# PowerInjectorSchematic.net
KiCad netlist of a schematic drawn in Altium Designer
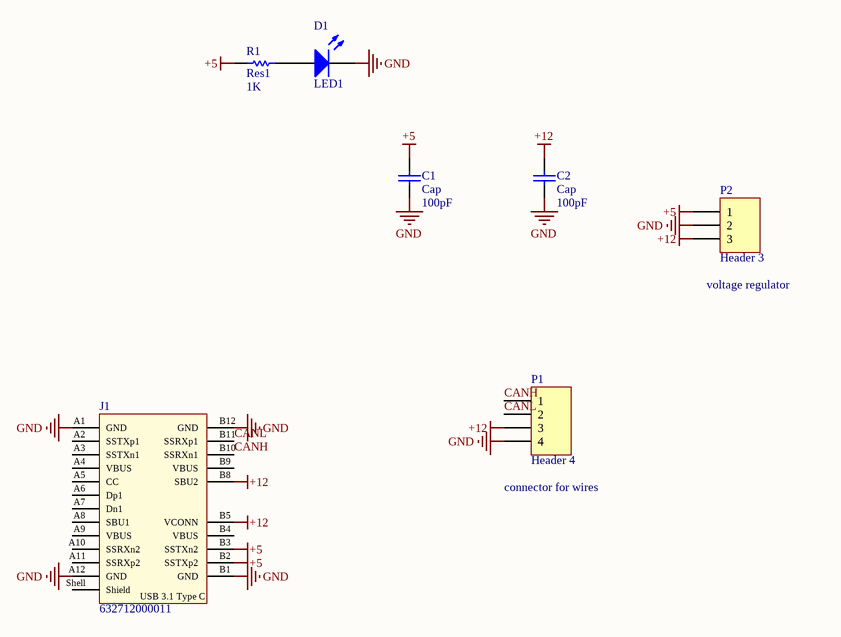
[diagram p0: PowerInjectorSchematic.SchDoc]

(export (version "E")
  (design (tool "Eeschema 10.0.6"))
  (components
    (comp (ref "C1")
      (value "Cap")
      (footprint "RAD-0.3")
      (description "Capacitor")
      (fields (field (name "ALTIUM_VALUE") "100pF") (field (name "PUBLISHER") "Altium Limited"))
      (libsource (lib "Miscellaneous Devices") (part "Cap"))
    )
    (comp (ref "C2")
      (value "Cap")
      (footprint "RAD-0.3")
      (description "Capacitor")
      (fields (field (name "ALTIUM_VALUE") "100pF") (field (name "PUBLISHER") "Altium Limited"))
      (libsource (lib "Miscellaneous Devices") (part "Cap"))
    )
    (comp (ref "D1")
      (value "LED1")
      (footprint "LED-1")
      (description "Typical RED GaAs LED")
      (fields (field (name "PUBLISHER") "Altium Limited"))
      (libsource (lib "Miscellaneous Devices") (part "LED1"))
    )
    (comp (ref "J1")
      (value "632712000011")
      (footprint "632712000011")
      (description "USB 3.1 Type C Plug Horizontal SMT WR-COM")
      (fields (field (name "PUBLISHER") "Wurth Elektronik"))
      (libsource (lib "ALTIUM-WR-COM-rev17a (1)") (part "632712000011"))
    )
    (comp (ref "P1")
      (value "Header 4")
      (footprint "HDR1X4")
      (description "Header, 4-Pin")
      (fields (field (name "PUBLISHER") "Altium Limited"))
      (libsource (lib "Miscellaneous Connectors") (part "Header 4"))
    )
    (comp (ref "P2")
      (value "Header 3")
      (footprint "HDR1X3")
      (description "Header, 3-Pin")
      (fields (field (name "PUBLISHER") "Altium Limited"))
      (libsource (lib "Miscellaneous Connectors") (part "Header 3"))
    )
    (comp (ref "R1")
      (value "Res1")
      (footprint "AXIAL-0.3")
      (description "Resistor")
      (fields (field (name "ALTIUM_VALUE") "1K") (field (name "PUBLISHER") "Altium Limited"))
      (libsource (lib "Miscellaneous Devices") (part "Res1"))
    )
  )
  (nets
    (net (code "1") (name "+5") (class "Default")
      (node (ref "C1") (pin "2") (pinfunction "2_2") (pintype "passive"))
      (node (ref "J1") (pin "B2") (pinfunction "SSTXp2_B2") (pintype "passive"))
      (node (ref "J1") (pin "B3") (pinfunction "SSTXn2_B3") (pintype "passive"))
      (node (ref "P2") (pin "1") (pinfunction "1_1") (pintype "passive"))
      (node (ref "R1") (pin "1") (pinfunction "1_1") (pintype "passive"))
    )
    (net (code "2") (name "+12") (class "Default")
      (node (ref "C2") (pin "2") (pinfunction "2_2") (pintype "passive"))
      (node (ref "J1") (pin "B5") (pinfunction "VCONN_B5") (pintype "passive"))
      (node (ref "J1") (pin "B8") (pinfunction "SBU2_B8") (pintype "passive"))
      (node (ref "P1") (pin "3") (pinfunction "3_3") (pintype "passive"))
      (node (ref "P2") (pin "3") (pinfunction "3_3") (pintype "passive"))
    )
    (net (code "3") (name "/CANH") (class "Default")
      (node (ref "J1") (pin "B10") (pinfunction "SSRXn1_B10") (pintype "passive"))
      (node (ref "P1") (pin "1") (pinfunction "1_1") (pintype "passive"))
    )
    (net (code "4") (name "/CANL") (class "Default")
      (node (ref "J1") (pin "B11") (pinfunction "SSRXp1_B11") (pintype "passive"))
      (node (ref "P1") (pin "2") (pinfunction "2_2") (pintype "passive"))
    )
    (net (code "5") (name "GND") (class "Default")
      (node (ref "C1") (pin "1") (pinfunction "1_1") (pintype "passive"))
      (node (ref "C2") (pin "1") (pinfunction "1_1") (pintype "passive"))
      (node (ref "D1") (pin "2") (pinfunction "K_2") (pintype "passive"))
      (node (ref "J1") (pin "A1") (pinfunction "GND_A1") (pintype "passive"))
      (node (ref "J1") (pin "A12") (pinfunction "GND_A12") (pintype "passive"))
      (node (ref "J1") (pin "B1") (pinfunction "GND_B1") (pintype "passive"))
      (node (ref "J1") (pin "B12") (pinfunction "GND_B12") (pintype "passive"))
      (node (ref "P1") (pin "4") (pinfunction "4_4") (pintype "passive"))
      (node (ref "P2") (pin "2") (pinfunction "2_2") (pintype "passive"))
    )
    (net (code "6") (name "Net-(D1-A)") (class "Default")
      (node (ref "D1") (pin "1") (pinfunction "A_1") (pintype "passive"))
      (node (ref "R1") (pin "2") (pinfunction "2_2") (pintype "passive"))
    )
    (net (code "7") (name "unconnected-(J1-CC-PadA5)") (class "Default")
      (node (ref "J1") (pin "A5") (pinfunction "CC_A5") (pintype "passive"))
    )
    (net (code "8") (name "unconnected-(J1-Dn1-PadA7)") (class "Default")
      (node (ref "J1") (pin "A7") (pinfunction "Dn1_A7") (pintype "passive"))
    )
    (net (code "9") (name "unconnected-(J1-Dp1-PadA6)") (class "Default")
      (node (ref "J1") (pin "A6") (pinfunction "Dp1_A6") (pintype "passive"))
    )
    (net (code "10") (name "unconnected-(J1-SBU1-PadA8)") (class "Default")
      (node (ref "J1") (pin "A8") (pinfunction "SBU1_A8") (pintype "passive"))
    )
    (net (code "11") (name "unconnected-(J1-SSRXn2-PadA10)") (class "Default")
      (node (ref "J1") (pin "A10") (pinfunction "SSRXn2_A10") (pintype "passive"))
    )
    (net (code "12") (name "unconnected-(J1-SSRXp2-PadA11)") (class "Default")
      (node (ref "J1") (pin "A11") (pinfunction "SSRXp2_A11") (pintype "passive"))
    )
    (net (code "13") (name "unconnected-(J1-SSTXn1-PadA3)") (class "Default")
      (node (ref "J1") (pin "A3") (pinfunction "SSTXn1_A3") (pintype "passive"))
    )
    (net (code "14") (name "unconnected-(J1-SSTXp1-PadA2)") (class "Default")
      (node (ref "J1") (pin "A2") (pinfunction "SSTXp1_A2") (pintype "passive"))
    )
    (net (code "15") (name "unconnected-(J1-Shield-PadShell)") (class "Default")
      (node (ref "J1") (pin "Shell") (pinfunction "Shield_Shell") (pintype "passive"))
    )
    (net (code "16") (name "unconnected-(J1-VBUS-PadA4)") (class "Default")
      (node (ref "J1") (pin "A4") (pinfunction "VBUS_A4") (pintype "passive"))
    )
    (net (code "17") (name "unconnected-(J1-VBUS-PadA9)") (class "Default")
      (node (ref "J1") (pin "A9") (pinfunction "VBUS_A9") (pintype "passive"))
    )
    (net (code "18") (name "unconnected-(J1-VBUS-PadB4)") (class "Default")
      (node (ref "J1") (pin "B4") (pinfunction "VBUS_B4") (pintype "passive"))
    )
    (net (code "19") (name "unconnected-(J1-VBUS-PadB9)") (class "Default")
      (node (ref "J1") (pin "B9") (pinfunction "VBUS_B9") (pintype "passive"))
    )
  )
)
